# Gate-Driver.net
KiCad netlist of a schematic drawn in Altium Designer
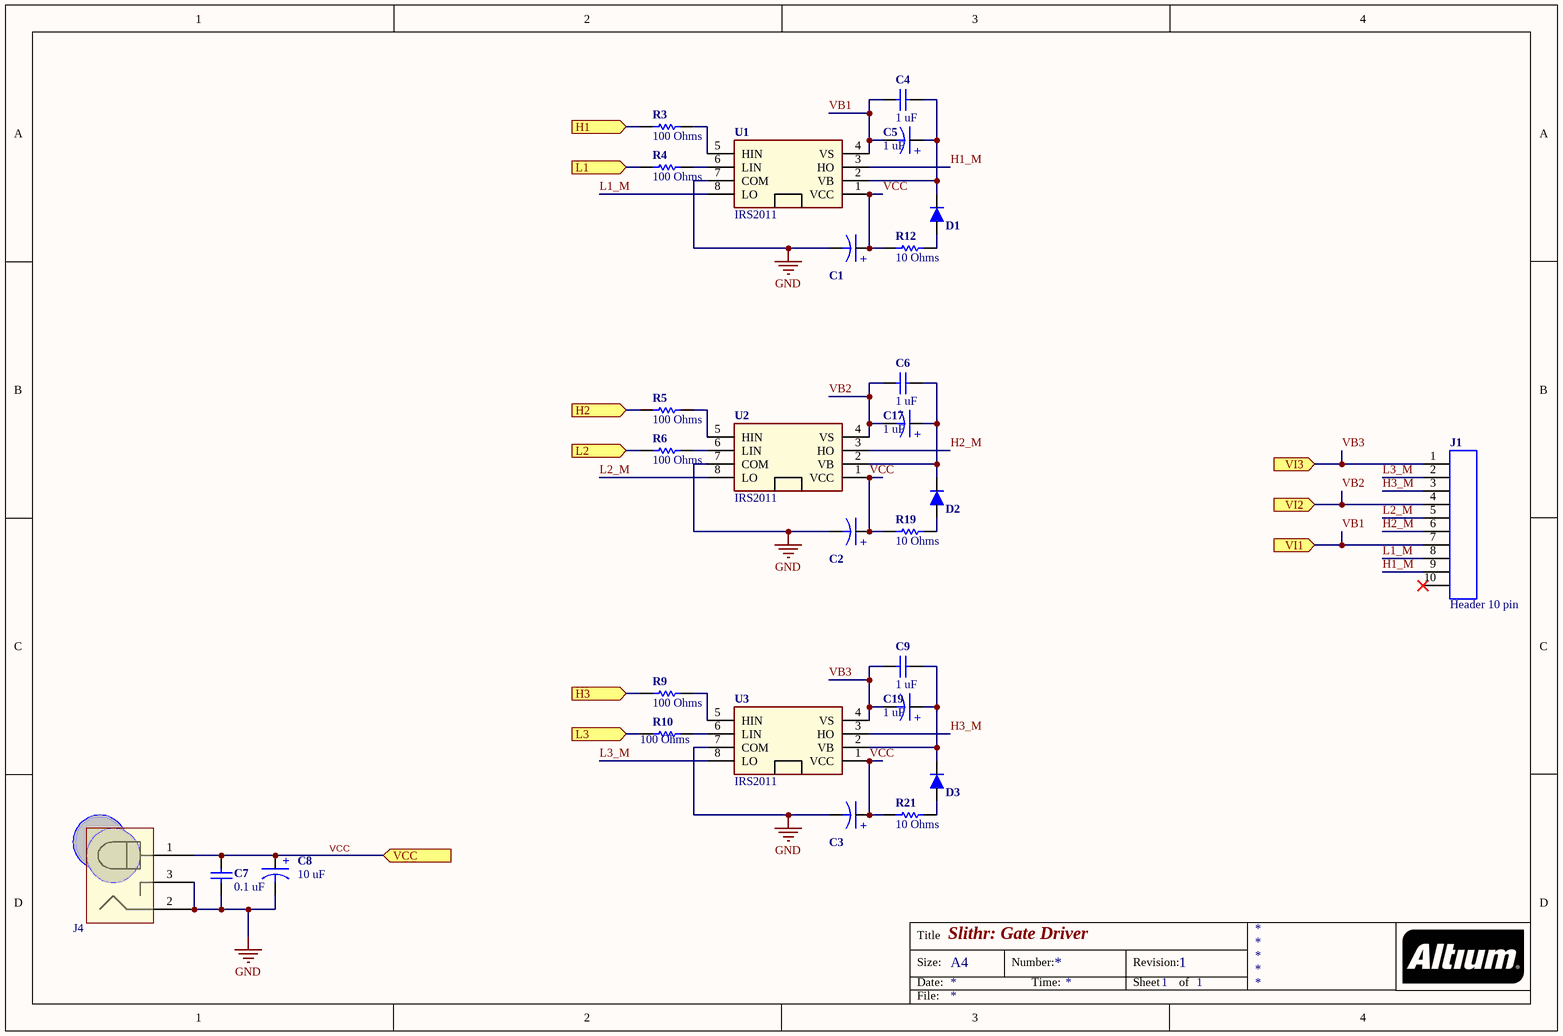
[diagram p0: Gate-Driver.SchDoc]

(export (version "E")
  (design (tool "Eeschema 10.0.6"))
  (components
    (comp (ref "C1")
      (value "~")
      (footprint "CAPMP3528X210N")
      (description "CAP TANT, 10uF, 16V, TANT-B")
      (fields (field (name "TOLERANCE") "10 %") (field (name "MANUFACTURER") "Vishay / Sprague"))
      (libsource (lib "CarlLibrary") (part "CAP-10uF-63V-TANTB-TC-B"))
    )
    (comp (ref "C2")
      (value "~")
      (footprint "CAPMP3528X210N")
      (description "CAP TANT, 10uF, 16V, TANT-B")
      (fields (field (name "TOLERANCE") "10 %") (field (name "MANUFACTURER") "Vishay / Sprague"))
      (libsource (lib "CarlLibrary") (part "CAP-10uF-63V-TANTB-TC-B"))
    )
    (comp (ref "C3")
      (value "~")
      (footprint "CAPMP3528X210N")
      (description "CAP TANT, 10uF, 16V, TANT-B")
      (fields (field (name "TOLERANCE") "10 %") (field (name "MANUFACTURER") "Vishay / Sprague"))
      (libsource (lib "CarlLibrary") (part "CAP-10uF-63V-TANTB-TC-B"))
    )
    (comp (ref "C4")
      (value "1 uF")
      (footprint "CAP-0805(2012)-R")
      (description "CAP CER 1 UF 50V 10% Y5V 0805")
      (fields (field (name "TOLERANCE") "10 %") (field (name "MANUFACTURER") "Yageo"))
      (libsource (lib "CarlLibrary") (part "CAP- 1 uF- 50 V-CER-0805(2012)"))
    )
    (comp (ref "C5")
      (value "1 uF")
      (footprint "CAPMP6032X280N")
      (description "CAP, 1uF, 63V, TANT-B")
      (fields
        (field (name "MANUFACTURER") "AVX")
        (field (name "MANUFACTURER PART NUMBER") "TCJC105M063R0300")
      )
      (libsource (lib "CarlLibrary") (part "CAP-1uF-63V-TANTB-TC-C"))
    )
    (comp (ref "C6")
      (value "1 uF")
      (footprint "CAP-0805(2012)-R")
      (description "CAP CER 1 UF 50V 10% Y5V 0805")
      (fields (field (name "TOLERANCE") "10 %") (field (name "MANUFACTURER") "Yageo"))
      (libsource (lib "CarlLibrary") (part "CAP- 1 uF- 50 V-CER-0805(2012)"))
    )
    (comp (ref "C7")
      (value "0.1 uF")
      (footprint "CAP-0402(1005)-R")
      (description "CAP CER 0.1 UF 16V 5% X7R 0402")
      (fields
        (field (name "MANUFACTURER") "Yageo")
        (field (name "MANUFACTURER PART NUMBER") "CC0402KRX7R7BB104")
      )
      (libsource (lib "CarlLibrary") (part "CAP- 0.1 uF- 16 V-CER-0402(1005)"))
    )
    (comp (ref "C8")
      (value "10 uF")
      (footprint "CAPE5.0mm")
      (description "CAP, 10uF, 25V, ALC, 20%")
      (fields
        (field (name "MANUFACTURER") "Vishay / Sprague")
        (field (name "MANUFACTURER PART NUMBER") "515D106M025JA6AE3")
      )
      (libsource (lib "CarlLibrary") (part "CAP-10uF-25V-ALC"))
    )
    (comp (ref "C9")
      (value "1 uF")
      (footprint "CAP-0805(2012)-R")
      (description "CAP CER 1 UF 50V 10% Y5V 0805")
      (fields (field (name "TOLERANCE") "10 %") (field (name "MANUFACTURER") "Yageo"))
      (libsource (lib "CarlLibrary") (part "CAP- 1 uF- 50 V-CER-0805(2012)"))
    )
    (comp (ref "C17")
      (value "1 uF")
      (footprint "CAPMP6032X280N")
      (description "CAP, 1uF, 63V, TANT-B")
      (fields
        (field (name "MANUFACTURER") "AVX")
        (field (name "MANUFACTURER PART NUMBER") "TCJC105M063R0300")
      )
      (libsource (lib "CarlLibrary") (part "CAP-1uF-63V-TANTB-TC-C"))
    )
    (comp (ref "C19")
      (value "1 uF")
      (footprint "CAPMP6032X280N")
      (description "CAP, 1uF, 63V, TANT-B")
      (fields
        (field (name "MANUFACTURER") "AVX")
        (field (name "MANUFACTURER PART NUMBER") "TCJC105M063R0300")
      )
      (libsource (lib "CarlLibrary") (part "CAP-1uF-63V-TANTB-TC-C"))
    )
    (comp (ref "D1")
      (value "~")
      (footprint "DO-214AC")
      (description "DIODE, ES1D Fairchild")
      (fields
        (field (name "MANUFACTURER") "Fairchild Semiconductor")
        (field (name "MANUFACTURER PART NUMBER") "ES1D")
      )
      (libsource (lib "CarlLibrary") (part "DIODE-ES1D"))
    )
    (comp (ref "D2")
      (value "~")
      (footprint "DO-214AC")
      (description "DIODE, ES1D Fairchild")
      (fields
        (field (name "MANUFACTURER") "Fairchild Semiconductor")
        (field (name "MANUFACTURER PART NUMBER") "ES1D")
      )
      (libsource (lib "CarlLibrary") (part "DIODE-ES1D"))
    )
    (comp (ref "D3")
      (value "~")
      (footprint "DO-214AC")
      (description "DIODE, ES1D Fairchild")
      (fields
        (field (name "MANUFACTURER") "Fairchild Semiconductor")
        (field (name "MANUFACTURER PART NUMBER") "ES1D")
      )
      (libsource (lib "CarlLibrary") (part "DIODE-ES1D"))
    )
    (comp (ref "J1")
      (value "Header 10 pin")
      (footprint "HEADER-10-100MIL")
      (description "Header, 10pin, .1 pitch")
      (fields (field (name "MANUFACTURER") "Molex") (field (name "MANUFACTURER PART NUMBER") "90136-1110"))
      (libsource (lib "CarlLibrary") (part "CON-10Pin-100Mil"))
    )
    (comp (ref "J4")
      (value "DC_Power-Jack")
      (footprint "Jack_M")
      (fields (field (name "MANUFACTURER") "CUI") (field (name "MANUFACTURER PART NUMBER") "PJ-002B"))
      (libsource (lib "CarlLibrary") (part "DC_Power-Jack"))
    )
    (comp (ref "R3")
      (value "100 Ohms")
      (footprint "R-0402(1005)-R")
      (description "RES 100 OHM 62.5 mW 0402(1005) SMD")
      (fields
        (field (name "MANUFACTURER") "Yageo")
        (field (name "MANUFACTURER PART NUMBER") "RC0402FR-07100RL")
      )
      (libsource (lib "CarlLibrary") (part "R-100-62.5 mW-0402(1005)"))
    )
    (comp (ref "R4")
      (value "100 Ohms")
      (footprint "R-0402(1005)-R")
      (description "RES 100 OHM 62.5 mW 0402(1005) SMD")
      (fields
        (field (name "MANUFACTURER") "Yageo")
        (field (name "MANUFACTURER PART NUMBER") "RC0402FR-07100RL")
      )
      (libsource (lib "CarlLibrary") (part "R-100-62.5 mW-0402(1005)"))
    )
    (comp (ref "R5")
      (value "100 Ohms")
      (footprint "R-0402(1005)-R")
      (description "RES 100 OHM 62.5 mW 0402(1005) SMD")
      (fields
        (field (name "MANUFACTURER") "Yageo")
        (field (name "MANUFACTURER PART NUMBER") "RC0402FR-07100RL")
      )
      (libsource (lib "CarlLibrary") (part "R-100-62.5 mW-0402(1005)"))
    )
    (comp (ref "R6")
      (value "100 Ohms")
      (footprint "R-0402(1005)-R")
      (description "RES 100 OHM 62.5 mW 0402(1005) SMD")
      (fields
        (field (name "MANUFACTURER") "Yageo")
        (field (name "MANUFACTURER PART NUMBER") "RC0402FR-07100RL")
      )
      (libsource (lib "CarlLibrary") (part "R-100-62.5 mW-0402(1005)"))
    )
    (comp (ref "R9")
      (value "100 Ohms")
      (footprint "R-0402(1005)-R")
      (description "RES 100 OHM 62.5 mW 0402(1005) SMD")
      (fields
        (field (name "MANUFACTURER") "Yageo")
        (field (name "MANUFACTURER PART NUMBER") "RC0402FR-07100RL")
      )
      (libsource (lib "CarlLibrary") (part "R-100-62.5 mW-0402(1005)"))
    )
    (comp (ref "R10")
      (value "100 Ohms")
      (footprint "R-0402(1005)-R")
      (description "RES 100 OHM 62.5 mW 0402(1005) SMD")
      (fields
        (field (name "MANUFACTURER") "Yageo")
        (field (name "MANUFACTURER PART NUMBER") "RC0402FR-07100RL")
      )
      (libsource (lib "CarlLibrary") (part "R-100-62.5 mW-0402(1005)"))
    )
    (comp (ref "R12")
      (value "10 Ohms")
      (footprint "R-0805(2012)-R")
      (description "RES 10 OHM 1/8W 0805 SMD")
      (fields
        (field (name "MANUFACTURER") "Yageo")
        (field (name "MANUFACTURER PART NUMBER") "RC0805FR-0710RL")
      )
      (libsource (lib "CarlLibrary") (part "R-10-125mW-0805"))
    )
    (comp (ref "R19")
      (value "10 Ohms")
      (footprint "R-0805(2012)-R")
      (description "RES 10 OHM 1/8W 0805 SMD")
      (fields
        (field (name "MANUFACTURER") "Yageo")
        (field (name "MANUFACTURER PART NUMBER") "RC0805FR-0710RL")
      )
      (libsource (lib "CarlLibrary") (part "R-10-125mW-0805"))
    )
    (comp (ref "R21")
      (value "10 Ohms")
      (footprint "R-0805(2012)-R")
      (description "RES 10 OHM 1/8W 0805 SMD")
      (fields
        (field (name "MANUFACTURER") "Yageo")
        (field (name "MANUFACTURER PART NUMBER") "RC0805FR-0710RL")
      )
      (libsource (lib "CarlLibrary") (part "R-10-125mW-0805"))
    )
    (comp (ref "U1")
      (value "IRS2011")
      (footprint "SOIC-8")
      (description "IC, HS/LS INDEPENDENT DRIVER")
      (fields
        (field (name "MANUFACTURER") "International Rectifier")
        (field (name "MANUFACTURER PART NUMBER") "IRS2011SPBF")
      )
      (libsource (lib "CarlLibrary") (part "IRS2011(S)PBF"))
    )
    (comp (ref "U2")
      (value "IRS2011")
      (footprint "SOIC-8")
      (description "IC, HS/LS INDEPENDENT DRIVER")
      (fields
        (field (name "MANUFACTURER") "International Rectifier")
        (field (name "MANUFACTURER PART NUMBER") "IRS2011SPBF")
      )
      (libsource (lib "CarlLibrary") (part "IRS2011(S)PBF"))
    )
    (comp (ref "U3")
      (value "IRS2011")
      (footprint "SOIC-8")
      (description "IC, HS/LS INDEPENDENT DRIVER")
      (fields
        (field (name "MANUFACTURER") "International Rectifier")
        (field (name "MANUFACTURER PART NUMBER") "IRS2011SPBF")
      )
      (libsource (lib "CarlLibrary") (part "IRS2011(S)PBF"))
    )
  )
  (nets
    (net (code "1") (name "/H1") (class "Default")
      (node (ref "R3") (pin "1") (pinfunction "1_1") (pintype "passive"))
    )
    (net (code "2") (name "/H1_M") (class "Default")
      (node (ref "J1") (pin "9") (pinfunction "9_9") (pintype "passive"))
      (node (ref "U1") (pin "3") (pinfunction "HO_3") (pintype "passive"))
    )
    (net (code "3") (name "/H2") (class "Default")
      (node (ref "R5") (pin "1") (pinfunction "1_1") (pintype "passive"))
    )
    (net (code "4") (name "/H2_M") (class "Default")
      (node (ref "J1") (pin "6") (pinfunction "6_6") (pintype "passive"))
      (node (ref "U2") (pin "3") (pinfunction "HO_3") (pintype "passive"))
    )
    (net (code "5") (name "/H3") (class "Default")
      (node (ref "R9") (pin "1") (pinfunction "1_1") (pintype "passive"))
    )
    (net (code "6") (name "/H3_M") (class "Default")
      (node (ref "J1") (pin "3") (pinfunction "3_3") (pintype "passive"))
      (node (ref "U3") (pin "3") (pinfunction "HO_3") (pintype "passive"))
    )
    (net (code "7") (name "/L1") (class "Default")
      (node (ref "R4") (pin "1") (pinfunction "1_1") (pintype "passive"))
    )
    (net (code "8") (name "/L1_M") (class "Default")
      (node (ref "J1") (pin "8") (pinfunction "8_8") (pintype "passive"))
      (node (ref "U1") (pin "8") (pinfunction "LO_8") (pintype "passive"))
    )
    (net (code "9") (name "/L2") (class "Default")
      (node (ref "R6") (pin "1") (pinfunction "1_1") (pintype "passive"))
    )
    (net (code "10") (name "/L2_M") (class "Default")
      (node (ref "J1") (pin "5") (pinfunction "5_5") (pintype "passive"))
      (node (ref "U2") (pin "8") (pinfunction "LO_8") (pintype "passive"))
    )
    (net (code "11") (name "/L3") (class "Default")
      (node (ref "R10") (pin "1") (pinfunction "1_1") (pintype "passive"))
    )
    (net (code "12") (name "/L3_M") (class "Default")
      (node (ref "J1") (pin "2") (pinfunction "2_2") (pintype "passive"))
      (node (ref "U3") (pin "8") (pinfunction "LO_8") (pintype "passive"))
    )
    (net (code "13") (name "/VB1") (class "Default")
      (node (ref "C4") (pin "1") (pinfunction "1_1") (pintype "passive"))
      (node (ref "C5") (pin "2") (pinfunction "NEGATIVE_2") (pintype "passive"))
      (node (ref "J1") (pin "7") (pinfunction "7_7") (pintype "passive"))
      (node (ref "U1") (pin "4") (pinfunction "VS_4") (pintype "power_in"))
    )
    (net (code "14") (name "/VB2") (class "Default")
      (node (ref "C17") (pin "2") (pinfunction "NEGATIVE_2") (pintype "passive"))
      (node (ref "C6") (pin "1") (pinfunction "1_1") (pintype "passive"))
      (node (ref "J1") (pin "4") (pinfunction "4_4") (pintype "passive"))
      (node (ref "U2") (pin "4") (pinfunction "VS_4") (pintype "power_in"))
    )
    (net (code "15") (name "/VB3") (class "Default")
      (node (ref "C19") (pin "2") (pinfunction "NEGATIVE_2") (pintype "passive"))
      (node (ref "C9") (pin "1") (pinfunction "1_1") (pintype "passive"))
      (node (ref "J1") (pin "1") (pinfunction "1_1") (pintype "passive"))
      (node (ref "U3") (pin "4") (pinfunction "VS_4") (pintype "power_in"))
    )
    (net (code "16") (name "/VCC") (class "Default")
      (node (ref "C1") (pin "1") (pinfunction "POSITIVE_1") (pintype "passive"))
      (node (ref "C2") (pin "1") (pinfunction "POSITIVE_1") (pintype "passive"))
      (node (ref "C3") (pin "1") (pinfunction "POSITIVE_1") (pintype "passive"))
      (node (ref "C7") (pin "1") (pinfunction "1_1") (pintype "passive"))
      (node (ref "C8") (pin "1") (pinfunction "POSITIVE_1") (pintype "passive"))
      (node (ref "J4") (pin "1") (pinfunction "Tip_1") (pintype "passive"))
      (node (ref "R12") (pin "0") (pinfunction "0_0") (pintype "passive"))
      (node (ref "R19") (pin "0") (pinfunction "0_0") (pintype "passive"))
      (node (ref "R21") (pin "0") (pinfunction "0_0") (pintype "passive"))
      (node (ref "U1") (pin "1") (pinfunction "VCC_1") (pintype "passive"))
      (node (ref "U2") (pin "1") (pinfunction "VCC_1") (pintype "passive"))
      (node (ref "U3") (pin "1") (pinfunction "VCC_1") (pintype "passive"))
    )
    (net (code "17") (name "GND") (class "Default")
      (node (ref "C1") (pin "2") (pinfunction "NEGATIVE_2") (pintype "passive"))
      (node (ref "C2") (pin "2") (pinfunction "NEGATIVE_2") (pintype "passive"))
      (node (ref "C3") (pin "2") (pinfunction "NEGATIVE_2") (pintype "passive"))
      (node (ref "C7") (pin "2") (pinfunction "2_2") (pintype "passive"))
      (node (ref "C8") (pin "2") (pinfunction "NEGATIVE_2") (pintype "passive"))
      (node (ref "J4") (pin "2") (pinfunction "Sleeve_2") (pintype "passive"))
      (node (ref "J4") (pin "3") (pinfunction "Insertion_Detection_3") (pintype "passive"))
      (node (ref "U1") (pin "7") (pinfunction "COM_7") (pintype "passive"))
      (node (ref "U2") (pin "7") (pinfunction "COM_7") (pintype "passive"))
      (node (ref "U3") (pin "7") (pinfunction "COM_7") (pintype "passive"))
    )
    (net (code "18") (name "Net-(C5-POSITIVE)") (class "Default")
      (node (ref "C4") (pin "2") (pinfunction "2_2") (pintype "passive"))
      (node (ref "C5") (pin "1") (pinfunction "POSITIVE_1") (pintype "passive"))
      (node (ref "D1") (pin "K") (pinfunction "CATHODE_K") (pintype "passive"))
      (node (ref "U1") (pin "2") (pinfunction "VB_2") (pintype "passive"))
    )
    (net (code "19") (name "Net-(C17-POSITIVE)") (class "Default")
      (node (ref "C17") (pin "1") (pinfunction "POSITIVE_1") (pintype "passive"))
      (node (ref "C6") (pin "2") (pinfunction "2_2") (pintype "passive"))
      (node (ref "D2") (pin "K") (pinfunction "CATHODE_K") (pintype "passive"))
      (node (ref "U2") (pin "2") (pinfunction "VB_2") (pintype "passive"))
    )
    (net (code "20") (name "Net-(C19-POSITIVE)") (class "Default")
      (node (ref "C19") (pin "1") (pinfunction "POSITIVE_1") (pintype "passive"))
      (node (ref "C9") (pin "2") (pinfunction "2_2") (pintype "passive"))
      (node (ref "D3") (pin "K") (pinfunction "CATHODE_K") (pintype "passive"))
      (node (ref "U3") (pin "2") (pinfunction "VB_2") (pintype "passive"))
    )
    (net (code "21") (name "Net-(D1-ANODE)") (class "Default")
      (node (ref "D1") (pin "A") (pinfunction "ANODE_A") (pintype "passive"))
      (node (ref "R12") (pin "1") (pinfunction "1_1") (pintype "passive"))
    )
    (net (code "22") (name "Net-(D2-ANODE)") (class "Default")
      (node (ref "D2") (pin "A") (pinfunction "ANODE_A") (pintype "passive"))
      (node (ref "R19") (pin "1") (pinfunction "1_1") (pintype "passive"))
    )
    (net (code "23") (name "Net-(D3-ANODE)") (class "Default")
      (node (ref "D3") (pin "A") (pinfunction "ANODE_A") (pintype "passive"))
      (node (ref "R21") (pin "1") (pinfunction "1_1") (pintype "passive"))
    )
    (net (code "24") (name "Net-(U1-HIN)") (class "Default")
      (node (ref "R3") (pin "2") (pinfunction "2_2") (pintype "passive"))
      (node (ref "U1") (pin "5") (pinfunction "HIN_5") (pintype "power_in"))
    )
    (net (code "25") (name "Net-(U1-LIN)") (class "Default")
      (node (ref "R4") (pin "2") (pinfunction "2_2") (pintype "passive"))
      (node (ref "U1") (pin "6") (pinfunction "LIN_6") (pintype "power_in"))
    )
    (net (code "26") (name "Net-(U2-HIN)") (class "Default")
      (node (ref "R5") (pin "2") (pinfunction "2_2") (pintype "passive"))
      (node (ref "U2") (pin "5") (pinfunction "HIN_5") (pintype "power_in"))
    )
    (net (code "27") (name "Net-(U2-LIN)") (class "Default")
      (node (ref "R6") (pin "2") (pinfunction "2_2") (pintype "passive"))
      (node (ref "U2") (pin "6") (pinfunction "LIN_6") (pintype "power_in"))
    )
    (net (code "28") (name "Net-(U3-HIN)") (class "Default")
      (node (ref "R9") (pin "2") (pinfunction "2_2") (pintype "passive"))
      (node (ref "U3") (pin "5") (pinfunction "HIN_5") (pintype "power_in"))
    )
    (net (code "29") (name "Net-(U3-LIN)") (class "Default")
      (node (ref "R10") (pin "2") (pinfunction "2_2") (pintype "passive"))
      (node (ref "U3") (pin "6") (pinfunction "LIN_6") (pintype "power_in"))
    )
    (net (code "30") (name "unconnected-(J1-Pad10)") (class "Default")
      (node (ref "J1") (pin "10") (pinfunction "10_10") (pintype "passive+no_connect"))
    )
  )
)
